# OpAmpLab.net
KiCad netlist of a schematic drawn in EAGLE
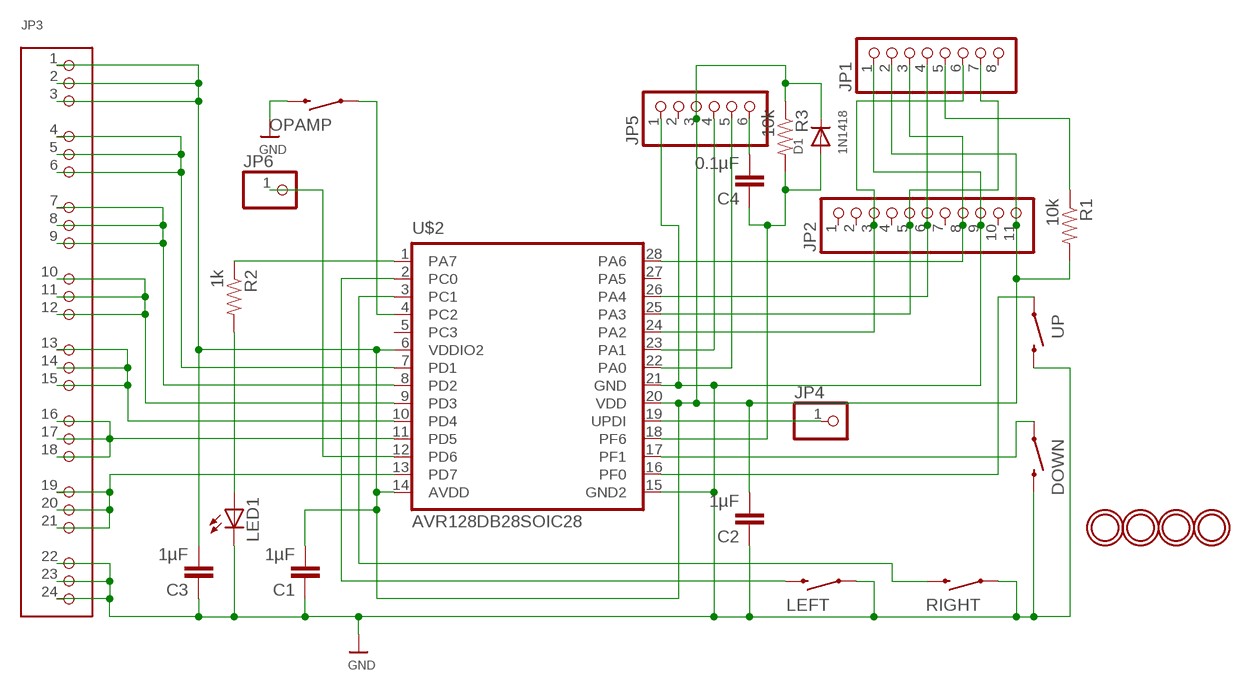
[diagram p0: schematic, sheet 1]

(export (version "E")
  (design (tool "Eeschema 10.0.6"))
  (components
    (comp (ref "C1")
      (value "1µF")
      (footprint "eagle-import:0805")
      (libsource (lib "eagle-import") (part "CAP0805"))
    )
    (comp (ref "C2")
      (value "1µF")
      (footprint "eagle-import:0805")
      (libsource (lib "eagle-import") (part "CAP0805"))
    )
    (comp (ref "C3")
      (value "1µF")
      (footprint "eagle-import:0805")
      (libsource (lib "eagle-import") (part "CAP0805"))
    )
    (comp (ref "C4")
      (value "0.1µF")
      (footprint "eagle-import:0805")
      (libsource (lib "eagle-import") (part "CAP0805"))
    )
    (comp (ref "D1")
      (value "1N1418")
      (footprint "eagle-import:SOD-323F")
      (libsource (lib "eagle-import") (part "DIODESOD-323F"))
    )
    (comp (ref "DOWN")
      (value "SWITCH-MOMENTARY-2PTH")
      (footprint "eagle-import:TACTILE-PTH")
      (libsource (lib "eagle-import") (part "SWITCH-MOMENTARY-2PTH"))
    )
    (comp (ref "JP1")
      (value "HEADER-1X8ROUND")
      (footprint "eagle-import:1X08_ROUND")
      (libsource (lib "eagle-import") (part "HEADER-1X8ROUND"))
    )
    (comp (ref "JP2")
      (value "HEADER-1X11")
      (footprint "eagle-import:1X11_ROUND")
      (libsource (lib "eagle-import") (part "HEADER-1X11"))
    )
    (comp (ref "JP3")
      (value "HEADER-3X08")
      (footprint "eagle-import:3X08")
      (libsource (lib "eagle-import") (part "HEADER-3X08"))
    )
    (comp (ref "JP4")
      (value "HEADER-1X1ROUND")
      (footprint "eagle-import:1X01_ROUND")
      (libsource (lib "eagle-import") (part "HEADER-1X1ROUND"))
    )
    (comp (ref "JP5")
      (value "HEADER-1X6ROUND")
      (footprint "eagle-import:1X06_ROUND")
      (libsource (lib "eagle-import") (part "HEADER-1X6ROUND"))
    )
    (comp (ref "JP6")
      (value "HEADER-1X1ROUND")
      (footprint "eagle-import:1X01_ROUND")
      (libsource (lib "eagle-import") (part "HEADER-1X1ROUND"))
    )
    (comp (ref "LED1")
      (value "LEDCHIPLED_0805")
      (footprint "eagle-import:CHIPLED_0805")
      (libsource (lib "eagle-import") (part "LEDCHIPLED_0805"))
    )
    (comp (ref "LEFT")
      (value "SWITCH-MOMENTARY-2PTH")
      (footprint "eagle-import:TACTILE-PTH")
      (libsource (lib "eagle-import") (part "SWITCH-MOMENTARY-2PTH"))
    )
    (comp (ref "OPAMP")
      (value "SWITCH-MOMENTARY-2PTH")
      (footprint "eagle-import:TACTILE-PTH")
      (libsource (lib "eagle-import") (part "SWITCH-MOMENTARY-2PTH"))
    )
    (comp (ref "R1")
      (value "10k")
      (footprint "eagle-import:0805")
      (libsource (lib "eagle-import") (part "0.3OHM-1/8W-1%(0805)"))
    )
    (comp (ref "R2")
      (value "1k")
      (footprint "eagle-import:0805")
      (libsource (lib "eagle-import") (part "0.3OHM-1/8W-1%(0805)"))
    )
    (comp (ref "R3")
      (value "10k")
      (footprint "eagle-import:0805")
      (libsource (lib "eagle-import") (part "0.3OHM-1/8W-1%(0805)"))
    )
    (comp (ref "RIGHT")
      (value "SWITCH-MOMENTARY-2PTH")
      (footprint "eagle-import:TACTILE-PTH")
      (libsource (lib "eagle-import") (part "SWITCH-MOMENTARY-2PTH"))
    )
    (comp (ref "U$1")
      (value "MOUNTINGHOLE2.5")
      (footprint "eagle-import:MOUNTINGHOLE_2.5_PLATED")
      (libsource (lib "eagle-import") (part "MOUNTINGHOLE2.5"))
    )
    (comp (ref "U$2")
      (value "AVR128DB28SOIC28")
      (footprint "eagle-import:SO-28W")
      (libsource (lib "eagle-import") (part "AVR128DB28SOIC28"))
    )
    (comp (ref "U$4")
      (value "MOUNTINGHOLE2.5")
      (footprint "eagle-import:MOUNTINGHOLE_2.5_PLATED")
      (libsource (lib "eagle-import") (part "MOUNTINGHOLE2.5"))
    )
    (comp (ref "U$5")
      (value "MOUNTINGHOLE2.5")
      (footprint "eagle-import:MOUNTINGHOLE_2.5_PLATED")
      (libsource (lib "eagle-import") (part "MOUNTINGHOLE2.5"))
    )
    (comp (ref "U$9")
      (value "MOUNTINGHOLE2.5")
      (footprint "eagle-import:MOUNTINGHOLE_2.5_PLATED")
      (libsource (lib "eagle-import") (part "MOUNTINGHOLE2.5"))
    )
    (comp (ref "UP")
      (value "SWITCH-MOMENTARY-2PTH")
      (footprint "eagle-import:TACTILE-PTH")
      (libsource (lib "eagle-import") (part "SWITCH-MOMENTARY-2PTH"))
    )
  )
  (nets
    (net (code "1") (name "GND") (class "Default")
      (node (ref "C1") (pin "1") (pinfunction "1_1") (pintype "passive"))
      (node (ref "C2") (pin "1") (pinfunction "1_1") (pintype "passive"))
      (node (ref "C3") (pin "1") (pinfunction "1_1") (pintype "passive"))
      (node (ref "DOWN") (pin "3") (pinfunction "2_3") (pintype "passive"))
      (node (ref "JP1") (pin "1") (pinfunction "1_1") (pintype "passive"))
      (node (ref "JP2") (pin "9") (pinfunction "9_9") (pintype "passive"))
      (node (ref "JP3") (pin "22") (pinfunction "22_22") (pintype "passive"))
      (node (ref "JP3") (pin "23") (pinfunction "23_23") (pintype "passive"))
      (node (ref "JP3") (pin "24") (pinfunction "24_24") (pintype "passive"))
      (node (ref "JP5") (pin "1") (pinfunction "1_1") (pintype "passive"))
      (node (ref "LED1") (pin "C") (pinfunction "C_C") (pintype "passive"))
      (node (ref "LEFT") (pin "1") (pinfunction "1_1") (pintype "passive"))
      (node (ref "OPAMP") (pin "3") (pinfunction "2_3") (pintype "passive"))
      (node (ref "RIGHT") (pin "1") (pinfunction "1_1") (pintype "passive"))
      (node (ref "U$2") (pin "15") (pinfunction "GND2_15") (pintype "bidirectional"))
      (node (ref "U$2") (pin "21") (pinfunction "GND_21") (pintype "bidirectional"))
      (node (ref "UP") (pin "3") (pinfunction "2_3") (pintype "passive"))
    )
    (net (code "2") (name "Net-(C4-Pad2)") (class "Default")
      (node (ref "C4") (pin "2") (pinfunction "2_2") (pintype "passive"))
      (node (ref "JP5") (pin "6") (pinfunction "6_6") (pintype "passive"))
    )
    (net (code "3") (name "Net-(JP1-Pad5)") (class "Default")
      (node (ref "JP1") (pin "5") (pinfunction "5_5") (pintype "passive"))
      (node (ref "R1") (pin "1") (pinfunction "1_1") (pintype "passive"))
    )
    (net (code "4") (name "Net-(LED1-PadA)") (class "Default")
      (node (ref "LED1") (pin "A") (pinfunction "A_A") (pintype "passive"))
      (node (ref "R2") (pin "2") (pinfunction "2_2") (pintype "passive"))
    )
    (net (code "5") (name "Net-(LEFT-2)") (class "Default")
      (node (ref "LEFT") (pin "3") (pinfunction "2_3") (pintype "passive"))
      (node (ref "U$2") (pin "2") (pinfunction "PC0_2") (pintype "bidirectional"))
    )
    (net (code "6") (name "Net-(RIGHT-2)") (class "Default")
      (node (ref "RIGHT") (pin "3") (pinfunction "2_3") (pintype "passive"))
      (node (ref "U$2") (pin "3") (pinfunction "PC1_3") (pintype "bidirectional"))
    )
    (net (code "7") (name "Net-(U$2-AVDD)") (class "Default")
      (node (ref "C1") (pin "2") (pinfunction "2_2") (pintype "passive"))
      (node (ref "C2") (pin "2") (pinfunction "2_2") (pintype "passive"))
      (node (ref "C3") (pin "2") (pinfunction "2_2") (pintype "passive"))
      (node (ref "D1") (pin "C") (pinfunction "C_C") (pintype "passive"))
      (node (ref "JP1") (pin "2") (pinfunction "2_2") (pintype "passive"))
      (node (ref "JP2") (pin "11") (pinfunction "11_11") (pintype "passive"))
      (node (ref "JP3") (pin "1") (pinfunction "1_1") (pintype "passive"))
      (node (ref "JP3") (pin "2") (pinfunction "2_2") (pintype "passive"))
      (node (ref "JP3") (pin "3") (pinfunction "3_3") (pintype "passive"))
      (node (ref "JP5") (pin "3") (pinfunction "3_3") (pintype "passive"))
      (node (ref "R1") (pin "2") (pinfunction "2_2") (pintype "passive"))
      (node (ref "R3") (pin "1") (pinfunction "1_1") (pintype "passive"))
      (node (ref "U$2") (pin "14") (pinfunction "AVDD_14") (pintype "bidirectional"))
      (node (ref "U$2") (pin "20") (pinfunction "VDD_20") (pintype "power_in"))
      (node (ref "U$2") (pin "6") (pinfunction "VDDIO2_6") (pintype "bidirectional"))
    )
    (net (code "8") (name "Net-(U$2-PA0)") (class "Default")
      (node (ref "JP5") (pin "5") (pinfunction "5_5") (pintype "passive"))
      (node (ref "U$2") (pin "22") (pinfunction "PA0_22") (pintype "bidirectional"))
    )
    (net (code "9") (name "Net-(U$2-PA1)") (class "Default")
      (node (ref "JP5") (pin "4") (pinfunction "4_4") (pintype "passive"))
      (node (ref "U$2") (pin "23") (pinfunction "PA1_23") (pintype "bidirectional"))
    )
    (net (code "10") (name "Net-(U$2-PA2)") (class "Default")
      (node (ref "JP1") (pin "6") (pinfunction "6_6") (pintype "passive"))
      (node (ref "JP2") (pin "3") (pinfunction "3_3") (pintype "passive"))
      (node (ref "U$2") (pin "24") (pinfunction "PA2_24") (pintype "bidirectional"))
    )
    (net (code "11") (name "Net-(U$2-PA3)") (class "Default")
      (node (ref "JP1") (pin "7") (pinfunction "7_7") (pintype "passive"))
      (node (ref "JP2") (pin "5") (pinfunction "5_5") (pintype "passive"))
      (node (ref "U$2") (pin "25") (pinfunction "PA3_25") (pintype "bidirectional"))
    )
    (net (code "12") (name "Net-(U$2-PA4)") (class "Default")
      (node (ref "JP1") (pin "4") (pinfunction "4_4") (pintype "passive"))
      (node (ref "JP2") (pin "6") (pinfunction "6_6") (pintype "passive"))
      (node (ref "U$2") (pin "26") (pinfunction "PA4_26") (pintype "bidirectional"))
    )
    (net (code "13") (name "Net-(U$2-PA6)") (class "Default")
      (node (ref "JP1") (pin "3") (pinfunction "3_3") (pintype "passive"))
      (node (ref "JP2") (pin "8") (pinfunction "8_8") (pintype "passive"))
      (node (ref "U$2") (pin "28") (pinfunction "PA6_28") (pintype "bidirectional"))
    )
    (net (code "14") (name "Net-(U$2-PA7)") (class "Default")
      (node (ref "R2") (pin "1") (pinfunction "1_1") (pintype "passive"))
      (node (ref "U$2") (pin "1") (pinfunction "PA7_1") (pintype "bidirectional"))
    )
    (net (code "15") (name "Net-(U$2-PC2)") (class "Default")
      (node (ref "OPAMP") (pin "1") (pinfunction "1_1") (pintype "passive"))
      (node (ref "U$2") (pin "4") (pinfunction "PC2_4") (pintype "bidirectional"))
    )
    (net (code "16") (name "Net-(U$2-PD1)") (class "Default")
      (node (ref "JP3") (pin "4") (pinfunction "4_4") (pintype "passive"))
      (node (ref "JP3") (pin "5") (pinfunction "5_5") (pintype "passive"))
      (node (ref "JP3") (pin "6") (pinfunction "6_6") (pintype "passive"))
      (node (ref "U$2") (pin "7") (pinfunction "PD1_7") (pintype "bidirectional"))
    )
    (net (code "17") (name "Net-(U$2-PD2)") (class "Default")
      (node (ref "JP3") (pin "7") (pinfunction "7_7") (pintype "passive"))
      (node (ref "JP3") (pin "8") (pinfunction "8_8") (pintype "passive"))
      (node (ref "JP3") (pin "9") (pinfunction "9_9") (pintype "passive"))
      (node (ref "U$2") (pin "8") (pinfunction "PD2_8") (pintype "power_in"))
    )
    (net (code "18") (name "Net-(U$2-PD3)") (class "Default")
      (node (ref "JP3") (pin "10") (pinfunction "10_10") (pintype "passive"))
      (node (ref "JP3") (pin "11") (pinfunction "11_11") (pintype "passive"))
      (node (ref "JP3") (pin "12") (pinfunction "12_12") (pintype "passive"))
      (node (ref "U$2") (pin "9") (pinfunction "PD3_9") (pintype "bidirectional"))
    )
    (net (code "19") (name "Net-(U$2-PD4)") (class "Default")
      (node (ref "JP3") (pin "13") (pinfunction "13_13") (pintype "passive"))
      (node (ref "JP3") (pin "14") (pinfunction "14_14") (pintype "passive"))
      (node (ref "JP3") (pin "15") (pinfunction "15_15") (pintype "passive"))
      (node (ref "U$2") (pin "10") (pinfunction "PD4_10") (pintype "bidirectional"))
    )
    (net (code "20") (name "Net-(U$2-PD5)") (class "Default")
      (node (ref "JP3") (pin "16") (pinfunction "16_16") (pintype "passive"))
      (node (ref "JP3") (pin "17") (pinfunction "17_17") (pintype "passive"))
      (node (ref "JP3") (pin "18") (pinfunction "18_18") (pintype "passive"))
      (node (ref "U$2") (pin "11") (pinfunction "PD5_11") (pintype "bidirectional"))
    )
    (net (code "21") (name "Net-(U$2-PD6)") (class "Default")
      (node (ref "JP6") (pin "1") (pinfunction "1_1") (pintype "passive"))
      (node (ref "U$2") (pin "12") (pinfunction "PD6_12") (pintype "bidirectional"))
    )
    (net (code "22") (name "Net-(U$2-PD7)") (class "Default")
      (node (ref "JP3") (pin "19") (pinfunction "19_19") (pintype "passive"))
      (node (ref "JP3") (pin "20") (pinfunction "20_20") (pintype "passive"))
      (node (ref "JP3") (pin "21") (pinfunction "21_21") (pintype "passive"))
      (node (ref "U$2") (pin "13") (pinfunction "PD7_13") (pintype "bidirectional"))
    )
    (net (code "23") (name "Net-(U$2-PF0)") (class "Default")
      (node (ref "U$2") (pin "16") (pinfunction "PF0_16") (pintype "bidirectional"))
      (node (ref "UP") (pin "1") (pinfunction "1_1") (pintype "passive"))
    )
    (net (code "24") (name "Net-(U$2-PF1)") (class "Default")
      (node (ref "DOWN") (pin "1") (pinfunction "1_1") (pintype "passive"))
      (node (ref "U$2") (pin "17") (pinfunction "PF1_17") (pintype "bidirectional"))
    )
    (net (code "25") (name "Net-(U$2-PF6)") (class "Default")
      (node (ref "C4") (pin "1") (pinfunction "1_1") (pintype "passive"))
      (node (ref "D1") (pin "A") (pinfunction "A_A") (pintype "passive"))
      (node (ref "R3") (pin "2") (pinfunction "2_2") (pintype "passive"))
      (node (ref "U$2") (pin "18") (pinfunction "PF6_18") (pintype "input"))
    )
    (net (code "26") (name "Net-(U$2-UPDI)") (class "Default")
      (node (ref "JP4") (pin "1") (pinfunction "1_1") (pintype "passive"))
      (node (ref "U$2") (pin "19") (pinfunction "UPDI_19") (pintype "power_in"))
    )
    (net (code "27") (name "unconnected-(JP1-Pad8)") (class "Default")
      (node (ref "JP1") (pin "8") (pinfunction "8_8") (pintype "passive"))
    )
    (net (code "28") (name "unconnected-(JP2-Pad1)") (class "Default")
      (node (ref "JP2") (pin "1") (pinfunction "1_1") (pintype "passive"))
    )
    (net (code "29") (name "unconnected-(JP2-Pad2)") (class "Default")
      (node (ref "JP2") (pin "2") (pinfunction "2_2") (pintype "passive"))
    )
    (net (code "30") (name "unconnected-(JP2-Pad4)") (class "Default")
      (node (ref "JP2") (pin "4") (pinfunction "4_4") (pintype "passive"))
    )
    (net (code "31") (name "unconnected-(JP2-Pad7)") (class "Default")
      (node (ref "JP2") (pin "7") (pinfunction "7_7") (pintype "passive"))
    )
    (net (code "32") (name "unconnected-(JP2-Pad10)") (class "Default")
      (node (ref "JP2") (pin "10") (pinfunction "10_10") (pintype "passive"))
    )
    (net (code "33") (name "unconnected-(JP5-Pad2)") (class "Default")
      (node (ref "JP5") (pin "2") (pinfunction "2_2") (pintype "passive"))
    )
    (net (code "34") (name "unconnected-(U$2-PA5-Pad27)") (class "Default")
      (node (ref "U$2") (pin "27") (pinfunction "PA5_27") (pintype "bidirectional"))
    )
    (net (code "35") (name "unconnected-(U$2-PC3-Pad5)") (class "Default")
      (node (ref "U$2") (pin "5") (pinfunction "PC3_5") (pintype "bidirectional"))
    )
  )
)
